# Tiny817_Xplained_Pro_current_measurement.net
KiCad netlist of a schematic drawn in Altium Designer
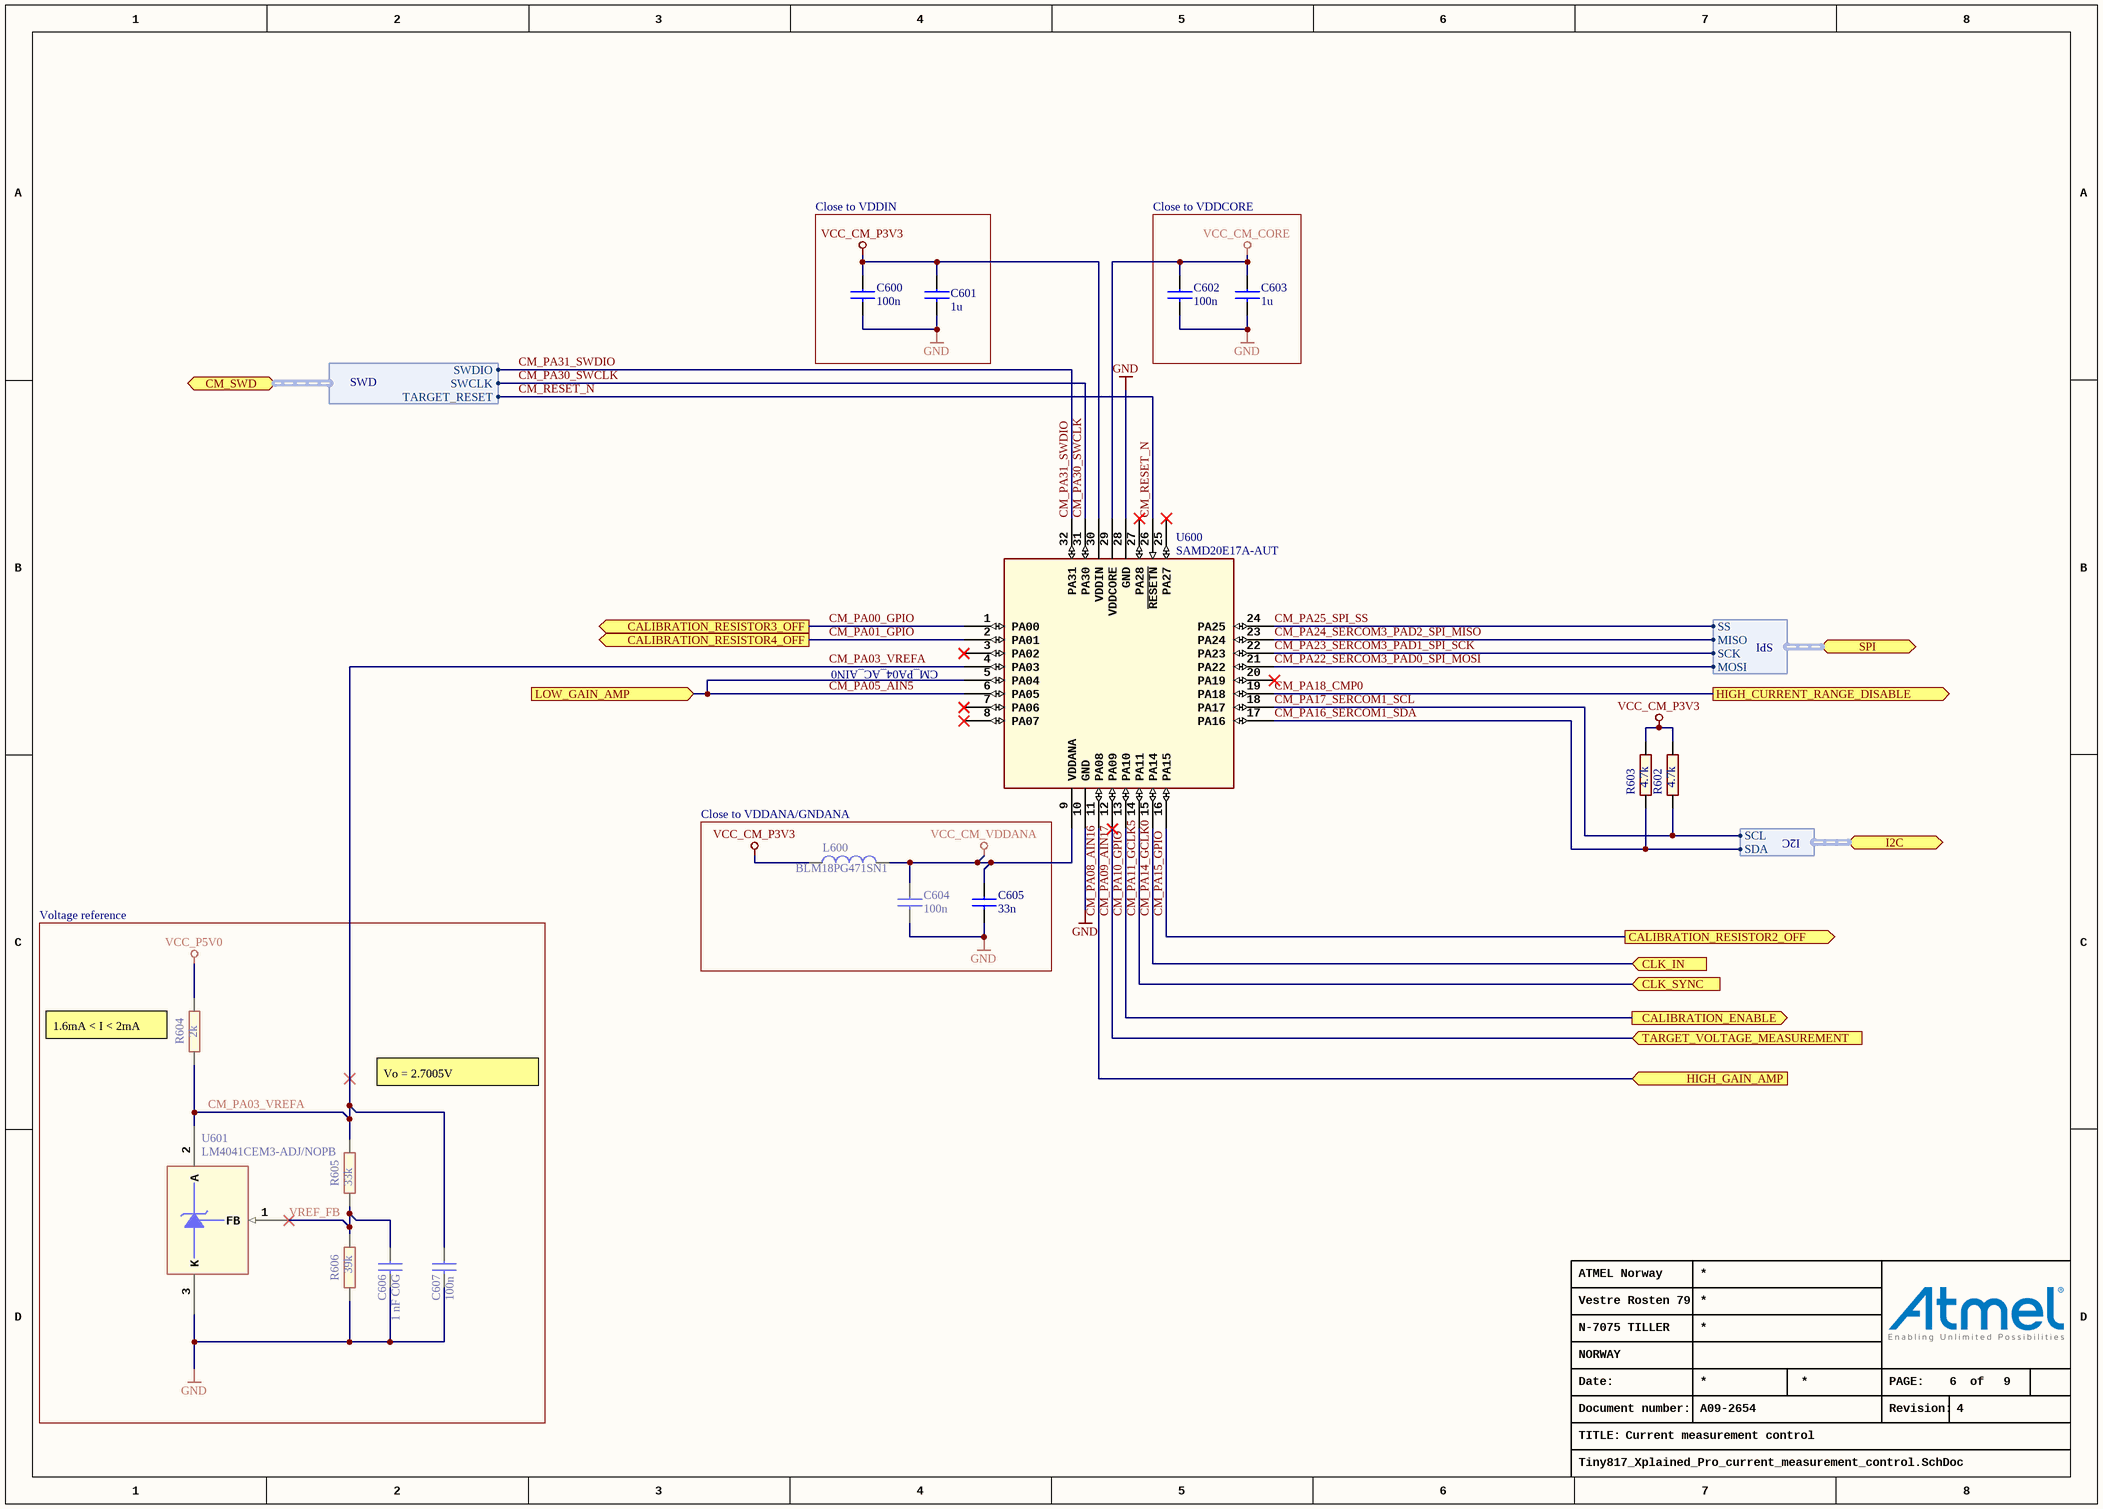
[diagram p0: Tiny817_Xplained_Pro_current_measurement_control.SchDoc]

(export (version "E")
  (design (tool "Eeschema 10.0.6"))
  (components
    (comp (ref "C600")
      (value "100n")
      (footprint "AP1-00053")
      (description "Ceramic capacitor, SMD 0402, X7R, 16V, +/-10%")
      (fields (field (name "TOLERANCE") "16V, +/-10%") (field (name "MANUFACTURER") "Kemet"))
      (libsource (lib "AltiumDbLib") (part "CAP-NONPOL"))
    )
    (comp (ref "C601")
      (value "1u")
      (footprint "AP1-00001")
      (description "Ceramic capacitor, SMD 0402, X5R, 6.3V, +/-10% (de26942)")
      (fields (field (name "TOLERANCE") "+/-10%") (field (name "MANUFACTURER") "Kemet"))
      (libsource (lib "AltiumDbLib") (part "CAP-NONPOL"))
    )
    (comp (ref "C602")
      (value "100n")
      (footprint "AP1-00053")
      (description "Ceramic capacitor, SMD 0402, X7R, 16V, +/-10%")
      (fields (field (name "TOLERANCE") "16V, +/-10%") (field (name "MANUFACTURER") "Kemet"))
      (libsource (lib "AltiumDbLib") (part "CAP-NONPOL"))
    )
    (comp (ref "C603")
      (value "1u")
      (footprint "AP1-00001")
      (description "Ceramic capacitor, SMD 0402, X5R, 6.3V, +/-10% (de26942)")
      (fields (field (name "TOLERANCE") "+/-10%") (field (name "MANUFACTURER") "Kemet"))
      (libsource (lib "AltiumDbLib") (part "CAP-NONPOL"))
    )
    (comp (ref "C604")
      (value "100n")
      (footprint "AP1-00053")
      (description "Ceramic capacitor, SMD 0402, X7R, 16V, +/-10%")
      (fields (field (name "TOLERANCE") "16V, +/-10%") (field (name "MANUFACTURER") "Kemet"))
      (libsource (lib "AltiumDbLib") (part "CAP-NONPOL"))
    )
    (comp (ref "C605")
      (value "33n")
      (footprint "AP1-00053")
      (description "Ceramic capacitor, SMD 0402, X7R, 25V, ±10%")
      (fields (field (name "TOLERANCE") "±10%(K)") (field (name "MANUFACTURER") "Murata"))
      (libsource (lib "AltiumDbLib") (part "CAP-NONPOL"))
    )
    (comp (ref "C606")
      (value "1 nF C0G")
      (footprint "AP1-00053")
      (description "Ceramic capacitor, SMD 0402, C0G, 50V, +/-5%")
      (fields (field (name "TOLERANCE") "5%") (field (name "MANUFACTURER") "Murata"))
      (libsource (lib "AltiumDbLib") (part "CAP-NONPOL"))
    )
    (comp (ref "C607")
      (value "100n")
      (footprint "AP1-00053")
      (description "Ceramic capacitor, SMD 0402, X7R, 16V, +/-10%")
      (fields (field (name "TOLERANCE") "16V, +/-10%") (field (name "MANUFACTURER") "Kemet"))
      (libsource (lib "AltiumDbLib") (part "CAP-NONPOL"))
    )
    (comp (ref "L600")
      (value "BLM18PG471SN1")
      (footprint "AP3-00005")
      (description "SMD RF inductor 0603. Z=470Ohm (@100MHz), Max R(dc)=0.65Ohm, Max current=1A")
      (fields (field (name "MANUFACTURER") "Murata"))
      (libsource (lib "AltiumDbLib") (part "INDUCTOR"))
    )
    (comp (ref "R602")
      (value "4.7k")
      (footprint "AP2-00011")
      (description "Thick film resistor, SMD 0402, 1/16W, 1%")
      (fields (field (name "TOLERANCE") "1 %") (field (name "MANUFACTURER") "PHYCOMP"))
      (libsource (lib "") (part "R2_1"))
    )
    (comp (ref "R603")
      (value "4.7k")
      (footprint "AP2-00011")
      (description "Thick film resistor, SMD 0402, 1/16W, 1%")
      (fields (field (name "TOLERANCE") "1 %") (field (name "MANUFACTURER") "PHYCOMP"))
      (libsource (lib "") (part "R2_1"))
    )
    (comp (ref "R604")
      (value "2k")
      (footprint "AP2-00011")
      (description "Thick film resistor, SMD 0402, 1/16W, 1%")
      (fields (field (name "TOLERANCE") "1 %"))
      (libsource (lib "AltiumDbLib") (part "R2"))
    )
    (comp (ref "R605")
      (value "33k")
      (footprint "AP2-00011")
      (description "Thick film resistor, SMD 0402, 1/16W, 1%")
      (fields (field (name "TOLERANCE") "1 %") (field (name "MANUFACTURER") "ASJ"))
      (libsource (lib "AltiumDbLib") (part "R2"))
    )
    (comp (ref "R606")
      (value "39k")
      (footprint "AP2-00011")
      (description "Thick film resistor, SMD 0402, 1/16W, 1%")
      (fields (field (name "TOLERANCE") "1 %") (field (name "MANUFACTURER") "ASJ"))
      (libsource (lib "AltiumDbLib") (part "R2"))
    )
    (comp (ref "U600")
      (value "SAMD20E17A-AUT")
      (footprint "AP6-00061")
      (description "Atmel 32bit RISC MCU 32 pin")
      (fields (field (name "MANUFACTURER") "ATMEL") (field (name "MPN") "ATSAMD20E17A-AUT"))
      (libsource (lib "AltiumDbLib") (part "SAMD20E"))
    )
    (comp (ref "U601")
      (value "LM4041CEM3-ADJ/NOPB")
      (footprint "AP5-00002")
      (description "Adjustable shunt voltage regulator, 1.24 to 10V out")
      (fields (field (name "MANUFACTURER") "Texas Instruments"))
      (libsource (lib "AltiumDbLib") (part "LM4041-ADJ"))
    )
  )
  (nets
    (net (code "4") (name "/CM_PA00_GPIO") (class "Default")
      (node (ref "U600") (pin "1") (pinfunction "PA00_1") (pintype "bidirectional"))
    )
    (net (code "5") (name "/CM_PA01_GPIO") (class "Default")
      (node (ref "U600") (pin "2") (pinfunction "PA01_2") (pintype "bidirectional"))
    )
    (net (code "6") (name "/CM_PA03_VREFA") (class "Default")
      (node (ref "C607") (pin "1") (pinfunction "1_1") (pintype "passive"))
      (node (ref "R604") (pin "1") (pinfunction "1_1") (pintype "passive"))
      (node (ref "R605") (pin "2") (pinfunction "2_2") (pintype "passive"))
      (node (ref "U600") (pin "4") (pinfunction "PA03_4") (pintype "bidirectional"))
      (node (ref "U601") (pin "2") (pinfunction "A_2") (pintype "power_in"))
    )
    (net (code "7") (name "/CM_PA05_AIN5") (class "Default")
      (node (ref "U600") (pin "5") (pinfunction "PA04_5") (pintype "bidirectional"))
      (node (ref "U600") (pin "6") (pinfunction "PA05_6") (pintype "bidirectional"))
    )
    (net (code "8") (name "/CM_PA08_AIN16") (class "Default")
      (node (ref "U600") (pin "11") (pinfunction "PA08_11") (pintype "bidirectional"))
    )
    (net (code "9") (name "/CM_PA09_AIN17") (class "Default")
      (node (ref "U600") (pin "12") (pinfunction "PA09_12") (pintype "bidirectional+no_connect"))
    )
    (net (code "10") (name "/CM_PA10_GPIO") (class "Default")
      (node (ref "U600") (pin "13") (pinfunction "PA10_13") (pintype "bidirectional"))
    )
    (net (code "11") (name "/CM_PA11_GCLK5") (class "Default")
      (node (ref "U600") (pin "14") (pinfunction "PA11_14") (pintype "bidirectional"))
    )
    (net (code "12") (name "/CM_PA14_GCLK0") (class "Default")
      (node (ref "U600") (pin "15") (pinfunction "PA14_15") (pintype "bidirectional"))
    )
    (net (code "13") (name "/CM_PA15_GPIO") (class "Default")
      (node (ref "U600") (pin "16") (pinfunction "PA15_16") (pintype "bidirectional"))
    )
    (net (code "14") (name "/CM_PA16_SERCOM1_SDA") (class "Default")
      (node (ref "R603") (pin "1") (pinfunction "1_1") (pintype "passive"))
      (node (ref "U600") (pin "17") (pinfunction "PA16_17") (pintype "bidirectional"))
    )
    (net (code "15") (name "/CM_PA17_SERCOM1_SCL") (class "Default")
      (node (ref "R602") (pin "1") (pinfunction "1_1") (pintype "passive"))
      (node (ref "U600") (pin "18") (pinfunction "PA17_18") (pintype "bidirectional"))
    )
    (net (code "16") (name "/CM_PA18_CMP0") (class "Default")
      (node (ref "U600") (pin "19") (pinfunction "PA18_19") (pintype "bidirectional"))
    )
    (net (code "17") (name "/CM_PA22_SERCOM3_PAD0_SPI_MOSI") (class "Default")
      (node (ref "U600") (pin "21") (pinfunction "PA22_21") (pintype "bidirectional"))
    )
    (net (code "18") (name "/CM_PA23_SERCOM3_PAD1_SPI_SCK") (class "Default")
      (node (ref "U600") (pin "22") (pinfunction "PA23_22") (pintype "bidirectional"))
    )
    (net (code "19") (name "/CM_PA24_SERCOM3_PAD2_SPI_MISO") (class "Default")
      (node (ref "U600") (pin "23") (pinfunction "PA24_23") (pintype "bidirectional"))
    )
    (net (code "20") (name "/CM_PA25_SPI_SS") (class "Default")
      (node (ref "U600") (pin "24") (pinfunction "PA25_24") (pintype "bidirectional"))
    )
    (net (code "21") (name "/CM_PA30_SWCLK") (class "Default")
      (node (ref "U600") (pin "31") (pinfunction "PA30_31") (pintype "bidirectional"))
    )
    (net (code "22") (name "/CM_PA31_SWDIO") (class "Default")
      (node (ref "U600") (pin "32") (pinfunction "PA31_32") (pintype "bidirectional"))
    )
    (net (code "23") (name "/CM_RESET_N") (class "Default")
      (node (ref "U600") (pin "26") (pinfunction "~{RESETN}_26") (pintype "input"))
    )
    (net (code "24") (name "/VREF_FB") (class "Default")
      (node (ref "C606") (pin "1") (pinfunction "1_1") (pintype "passive"))
      (node (ref "R605") (pin "1") (pinfunction "1_1") (pintype "passive"))
      (node (ref "R606") (pin "2") (pinfunction "2_2") (pintype "passive"))
      (node (ref "U601") (pin "1") (pinfunction "FB_1") (pintype "input"))
    )
    (net (code "28") (name "GND") (class "Default")
      (node (ref "C600") (pin "2") (pinfunction "2_2") (pintype "passive"))
      (node (ref "C601") (pin "2") (pinfunction "2_2") (pintype "passive"))
      (node (ref "C602") (pin "2") (pinfunction "2_2") (pintype "passive"))
      (node (ref "C603") (pin "2") (pinfunction "2_2") (pintype "passive"))
      (node (ref "C604") (pin "2") (pinfunction "2_2") (pintype "passive"))
      (node (ref "C605") (pin "2") (pinfunction "2_2") (pintype "passive"))
      (node (ref "C606") (pin "2") (pinfunction "2_2") (pintype "passive"))
      (node (ref "C607") (pin "2") (pinfunction "2_2") (pintype "passive"))
      (node (ref "R606") (pin "1") (pinfunction "1_1") (pintype "passive"))
      (node (ref "U600") (pin "10") (pinfunction "GND_10") (pintype "power_in"))
      (node (ref "U600") (pin "28") (pinfunction "GND_28") (pintype "power_in"))
      (node (ref "U601") (pin "3") (pinfunction "K_3") (pintype "power_in"))
    )
    (net (code "29") (name "VCC_CM_CORE") (class "Default")
      (node (ref "C602") (pin "1") (pinfunction "1_1") (pintype "passive"))
      (node (ref "C603") (pin "1") (pinfunction "1_1") (pintype "passive"))
      (node (ref "U600") (pin "29") (pinfunction "VDDCORE_29") (pintype "power_in"))
    )
    (net (code "30") (name "VCC_CM_P3V3") (class "Default")
      (node (ref "C600") (pin "1") (pinfunction "1_1") (pintype "passive"))
      (node (ref "C601") (pin "1") (pinfunction "1_1") (pintype "passive"))
      (node (ref "L600") (pin "1") (pinfunction "1_1") (pintype "passive"))
      (node (ref "R602") (pin "2") (pinfunction "2_2") (pintype "passive"))
      (node (ref "R603") (pin "2") (pinfunction "2_2") (pintype "passive"))
      (node (ref "U600") (pin "30") (pinfunction "VDDIN_30") (pintype "power_in"))
    )
    (net (code "31") (name "VCC_CM_VDDANA") (class "Default")
      (node (ref "C604") (pin "1") (pinfunction "1_1") (pintype "passive"))
      (node (ref "C605") (pin "1") (pinfunction "1_1") (pintype "passive"))
      (node (ref "L600") (pin "2") (pinfunction "2_2") (pintype "passive"))
      (node (ref "U600") (pin "9") (pinfunction "VDDANA_9") (pintype "power_in"))
    )
    (net (code "32") (name "VCC_P5V0") (class "Default")
      (node (ref "R604") (pin "2") (pinfunction "2_2") (pintype "passive"))
    )
    (net (code "33") (name "unconnected-(U600-PA02-Pad3)") (class "Default")
      (node (ref "U600") (pin "3") (pinfunction "PA02_3") (pintype "bidirectional+no_connect"))
    )
    (net (code "34") (name "unconnected-(U600-PA06-Pad7)") (class "Default")
      (node (ref "U600") (pin "7") (pinfunction "PA06_7") (pintype "bidirectional+no_connect"))
    )
    (net (code "35") (name "unconnected-(U600-PA07-Pad8)") (class "Default")
      (node (ref "U600") (pin "8") (pinfunction "PA07_8") (pintype "bidirectional+no_connect"))
    )
    (net (code "36") (name "unconnected-(U600-PA19-Pad20)") (class "Default")
      (node (ref "U600") (pin "20") (pinfunction "PA19_20") (pintype "bidirectional+no_connect"))
    )
    (net (code "37") (name "unconnected-(U600-PA27-Pad25)") (class "Default")
      (node (ref "U600") (pin "25") (pinfunction "PA27_25") (pintype "bidirectional+no_connect"))
    )
    (net (code "38") (name "unconnected-(U600-PA28-Pad27)") (class "Default")
      (node (ref "U600") (pin "27") (pinfunction "PA28_27") (pintype "bidirectional+no_connect"))
    )
  )
)
